# MCU_PWR.net
KiCad netlist of a schematic drawn in Altium Designer
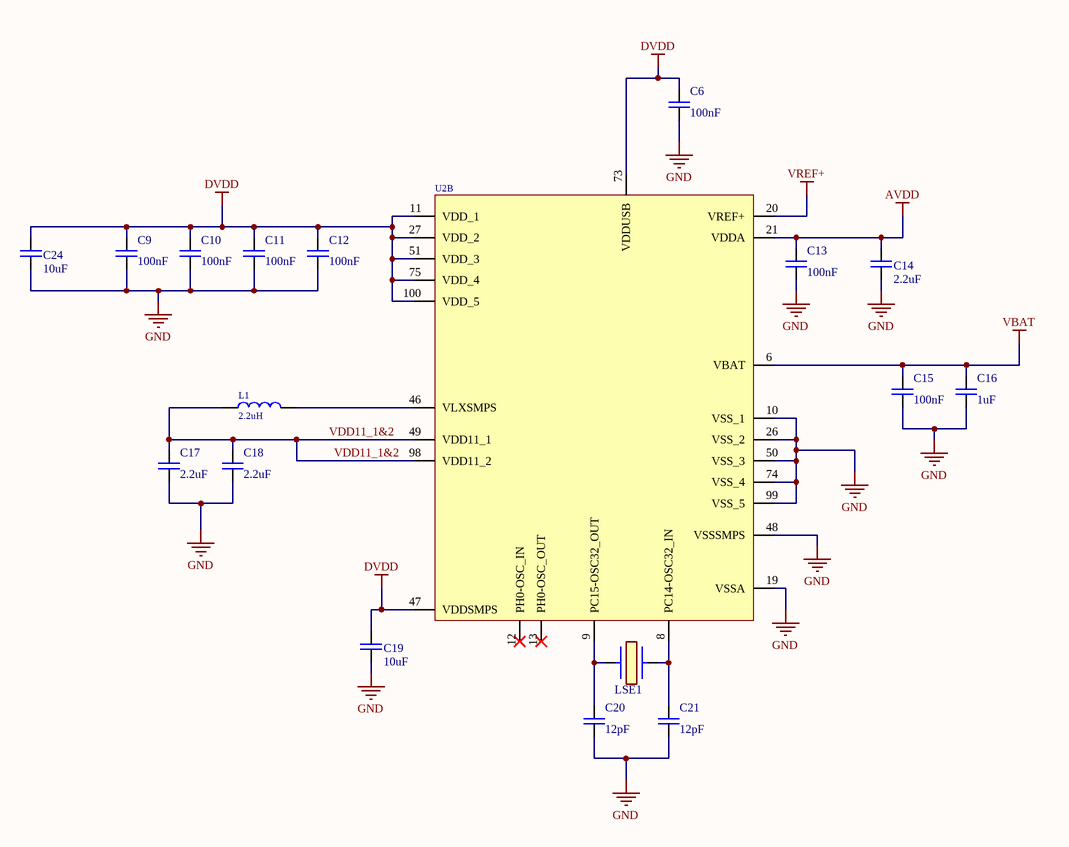
[diagram p0: MCU_PWR.SchDoc]

(export (version "E")
  (design (tool "Eeschema 10.0.6"))
  (components
    (comp (ref "C6")
      (value "100nF")
      (footprint "CAP_SM0805_YAGEOCC2_N")
      (description "CAP 100nF SM0805 X7R 50V YAGEO CC2")
      (fields
        (field (name "MANUFACTURER") "Yageo")
        (field (name "MANUFACTURER PART NUMBER") "CC0805KRX7R9BB104")
      )
      (libsource (lib "Yageo") (part "CC0805KRX7R9BB104"))
    )
    (comp (ref "C9")
      (value "100nF")
      (footprint "CAP_SM0805_YAGEOCC2_N")
      (description "CAP 100nF SM0805 X7R 50V YAGEO CC2")
      (fields
        (field (name "MANUFACTURER") "Yageo")
        (field (name "MANUFACTURER PART NUMBER") "CC0805KRX7R9BB104")
      )
      (libsource (lib "Yageo") (part "CC0805KRX7R9BB104"))
    )
    (comp (ref "C10")
      (value "100nF")
      (footprint "CAP_SM0805_YAGEOCC2_N")
      (description "CAP 100nF SM0805 X7R 50V YAGEO CC2")
      (fields
        (field (name "MANUFACTURER") "Yageo")
        (field (name "MANUFACTURER PART NUMBER") "CC0805KRX7R9BB104")
      )
      (libsource (lib "Yageo") (part "CC0805KRX7R9BB104"))
    )
    (comp (ref "C11")
      (value "100nF")
      (footprint "CAP_SM0805_YAGEOCC2_N")
      (description "CAP 100nF SM0805 X7R 50V YAGEO CC2")
      (fields
        (field (name "MANUFACTURER") "Yageo")
        (field (name "MANUFACTURER PART NUMBER") "CC0805KRX7R9BB104")
      )
      (libsource (lib "Yageo") (part "CC0805KRX7R9BB104"))
    )
    (comp (ref "C12")
      (value "100nF")
      (footprint "CAP_SM0805_YAGEOCC2_N")
      (description "CAP 100nF SM0805 X7R 50V YAGEO CC2")
      (fields
        (field (name "MANUFACTURER") "Yageo")
        (field (name "MANUFACTURER PART NUMBER") "CC0805KRX7R9BB104")
      )
      (libsource (lib "Yageo") (part "CC0805KRX7R9BB104"))
    )
    (comp (ref "C13")
      (value "100nF")
      (footprint "CAP_SM0805_YAGEOCC2_N")
      (description "CAP 100nF SM0805 X7R 50V YAGEO CC2")
      (fields
        (field (name "MANUFACTURER") "Yageo")
        (field (name "MANUFACTURER PART NUMBER") "CC0805KRX7R9BB104")
      )
      (libsource (lib "Yageo") (part "CC0805KRX7R9BB104"))
    )
    (comp (ref "C14")
      (value "2.2uF")
      (footprint "CAP_SM0805_YAGEOCC2_N")
      (description "CAP 2u2F SM0805 X7R 25V YAGEO CC2")
      (fields
        (field (name "MANUFACTURER") "Yageo")
        (field (name "MANUFACTURER PART NUMBER") "CC0805KKX7R8BB225")
      )
      (libsource (lib "Yageo") (part "CC0805KKX7R8BB225"))
    )
    (comp (ref "C15")
      (value "100nF")
      (footprint "CAP_SM0805_YAGEOCC2_N")
      (description "CAP 100nF SM0805 X7R 50V YAGEO CC2")
      (fields
        (field (name "MANUFACTURER") "Yageo")
        (field (name "MANUFACTURER PART NUMBER") "CC0805KRX7R9BB104")
      )
      (libsource (lib "Yageo") (part "CC0805KRX7R9BB104"))
    )
    (comp (ref "C16")
      (value "1uF")
      (footprint "CAP_SM0805_YAGEOCC2_N")
      (description "CAP 1uF SM0805 X7R 25V YAGEO CC2")
      (fields
        (field (name "MANUFACTURER") "Yageo")
        (field (name "MANUFACTURER PART NUMBER") "CC0805KKX7R8BB105")
      )
      (libsource (lib "Yageo") (part "CC0805KKX7R8BB105"))
    )
    (comp (ref "C17")
      (value "2.2uF")
      (footprint "CAP_SM0805_YAGEOCC2_N")
      (description "CAP 2u2F SM0805 X7R 25V YAGEO CC2")
      (fields
        (field (name "MANUFACTURER") "Yageo")
        (field (name "MANUFACTURER PART NUMBER") "CC0805KKX7R8BB225")
      )
      (libsource (lib "Yageo") (part "CC0805KKX7R8BB225"))
    )
    (comp (ref "C18")
      (value "2.2uF")
      (footprint "CAP_SM0805_YAGEOCC2_N")
      (description "CAP 2u2F SM0805 X7R 25V YAGEO CC2")
      (fields
        (field (name "MANUFACTURER") "Yageo")
        (field (name "MANUFACTURER PART NUMBER") "CC0805KKX7R8BB225")
      )
      (libsource (lib "Yageo") (part "CC0805KKX7R8BB225"))
    )
    (comp (ref "C19")
      (value "10uF")
      (footprint "CAP_SM0805_YAGEOCC2_N")
      (description "CAP 10uF SM0805 X5R 25V YAGEO")
      (fields
        (field (name "MANUFACTURER") "Yageo")
        (field (name "MANUFACTURER PART NUMBER") "CC0805KKX5R8BB106")
      )
      (libsource (lib "Yageo") (part "CC0805KKX5R8BB106"))
    )
    (comp (ref "C20")
      (value "12pF")
      (footprint "CAP_SM0805_YAGEOCC2_N")
      (description "CAP 12pF SM0805 NPO 50V YAGEO CC2")
      (fields
        (field (name "MANUFACTURER") "Yageo")
        (field (name "MANUFACTURER PART NUMBER") "CC0805JRNPO9BN120")
      )
      (libsource (lib "Yageo") (part "CC0805JRNPO9BN120"))
    )
    (comp (ref "C21")
      (value "12pF")
      (footprint "CAP_SM0805_YAGEOCC2_N")
      (description "CAP 12pF SM0805 NPO 50V YAGEO CC2")
      (fields
        (field (name "MANUFACTURER") "Yageo")
        (field (name "MANUFACTURER PART NUMBER") "CC0805JRNPO9BN120")
      )
      (libsource (lib "Yageo") (part "CC0805JRNPO9BN120"))
    )
    (comp (ref "C24")
      (value "10uF")
      (footprint "CAP_SM0805_YAGEOCC2_N")
      (description "CAP 10uF SM0805 X5R 25V YAGEO")
      (fields
        (field (name "MANUFACTURER") "Yageo")
        (field (name "MANUFACTURER PART NUMBER") "CC0805KKX5R8BB106")
      )
      (libsource (lib "Yageo") (part "CC0805KKX5R8BB106"))
    )
    (comp (ref "L1")
      (value "2.2uH")
      (footprint "LQM21PN2R2MGHL")
      (description "Inductores de potencia - SMD 2.2 UH 20%")
      (fields
        (field (name "MANUFACTURER") "Murata Electronics")
        (field (name "MANUFACTURER PART NUMBER") "LQM21PN2R2MGHL")
      )
      (libsource (lib "Inductores") (part "LQM21PN2R2MGHL"))
    )
    (comp (ref "LSE1")
      (value "32,768 kHz")
      (footprint "SC-32S32.768kHz20PPM12.5pF")
      (description "Cristal Oscilador 32.768 kHz, 12.5pF")
      (fields
        (field (name "MANUFACTURER") "Seiko")
        (field (name "MANUFACTURER PART NUMBER") "SC32S-12.5PF20PPM")
      )
      (libsource (lib "Osciladores") (part "SC32S-12.5PF20PPM"))
    )
    (comp (ref "U2")
      (value "STM32U575VI_1")
      (footprint "STM32U575VI")
      (fields (field (name "MANUFACTURER") "ST") (field (name "MANUFACTURER PART NUMBER") "STM32U575VIT6Q"))
      (libsource (lib "Microcontroladores") (part "STM32U575VI_1"))
    )
  )
  (nets
    (net (code "1") (name "/VDD11_1&2") (class "Default")
      (node (ref "C17") (pin "1") (pintype "passive"))
      (node (ref "C18") (pin "1") (pintype "passive"))
      (node (ref "L1") (pin "1") (pinfunction "1_1") (pintype "passive"))
      (node (ref "U2") (pin "49") (pinfunction "VDD11_1_49") (pintype "passive"))
      (node (ref "U2") (pin "98") (pinfunction "VDD11_2_98") (pintype "passive"))
    )
    (net (code "2") (name "AVDD") (class "Default")
      (node (ref "C13") (pin "1") (pintype "passive"))
      (node (ref "C14") (pin "1") (pintype "passive"))
      (node (ref "U2") (pin "21") (pinfunction "VDDA_21") (pintype "passive"))
    )
    (net (code "3") (name "DVDD") (class "Default")
      (node (ref "C10") (pin "1") (pintype "passive"))
      (node (ref "C11") (pin "1") (pintype "passive"))
      (node (ref "C12") (pin "1") (pintype "passive"))
      (node (ref "C19") (pin "1") (pintype "passive"))
      (node (ref "C24") (pin "1") (pintype "passive"))
      (node (ref "C6") (pin "1") (pintype "passive"))
      (node (ref "C9") (pin "1") (pintype "passive"))
      (node (ref "U2") (pin "100") (pinfunction "VDD_5_100") (pintype "passive"))
      (node (ref "U2") (pin "11") (pinfunction "VDD_1_11") (pintype "passive"))
      (node (ref "U2") (pin "27") (pinfunction "VDD_2_27") (pintype "passive"))
      (node (ref "U2") (pin "47") (pinfunction "VDDSMPS_47") (pintype "passive"))
      (node (ref "U2") (pin "51") (pinfunction "VDD_3_51") (pintype "passive"))
      (node (ref "U2") (pin "73") (pinfunction "VDDUSB_73") (pintype "passive"))
      (node (ref "U2") (pin "75") (pinfunction "VDD_4_75") (pintype "passive"))
    )
    (net (code "4") (name "GND") (class "Default")
      (node (ref "C10") (pin "2") (pintype "passive"))
      (node (ref "C11") (pin "2") (pintype "passive"))
      (node (ref "C12") (pin "2") (pintype "passive"))
      (node (ref "C13") (pin "2") (pintype "passive"))
      (node (ref "C14") (pin "2") (pintype "passive"))
      (node (ref "C15") (pin "2") (pintype "passive"))
      (node (ref "C16") (pin "2") (pintype "passive"))
      (node (ref "C17") (pin "2") (pintype "passive"))
      (node (ref "C18") (pin "2") (pintype "passive"))
      (node (ref "C19") (pin "2") (pintype "passive"))
      (node (ref "C20") (pin "2") (pintype "passive"))
      (node (ref "C21") (pin "2") (pintype "passive"))
      (node (ref "C24") (pin "2") (pintype "passive"))
      (node (ref "C6") (pin "2") (pintype "passive"))
      (node (ref "C9") (pin "2") (pintype "passive"))
      (node (ref "U2") (pin "10") (pinfunction "VSS_1_10") (pintype "passive"))
      (node (ref "U2") (pin "19") (pinfunction "VSSA_19") (pintype "passive"))
      (node (ref "U2") (pin "26") (pinfunction "VSS_2_26") (pintype "passive"))
      (node (ref "U2") (pin "48") (pinfunction "VSSSMPS_48") (pintype "passive"))
      (node (ref "U2") (pin "50") (pinfunction "VSS_3_50") (pintype "passive"))
      (node (ref "U2") (pin "74") (pinfunction "VSS_4_74") (pintype "passive"))
      (node (ref "U2") (pin "99") (pinfunction "VSS_5_99") (pintype "passive"))
    )
    (net (code "5") (name "Net-(U2B-PC14-OSC32_IN)") (class "Default")
      (node (ref "C21") (pin "1") (pintype "passive"))
      (node (ref "LSE1") (pin "2") (pinfunction "2_2") (pintype "passive"))
      (node (ref "U2") (pin "8") (pinfunction "PC14-OSC32_IN_8") (pintype "passive"))
    )
    (net (code "6") (name "Net-(U2B-PC15-OSC32_OUT)") (class "Default")
      (node (ref "C20") (pin "1") (pintype "passive"))
      (node (ref "LSE1") (pin "1") (pinfunction "1_1") (pintype "passive"))
      (node (ref "U2") (pin "9") (pinfunction "PC15-OSC32_OUT_9") (pintype "passive"))
    )
    (net (code "7") (name "Net-(U2B-VLXSMPS)") (class "Default")
      (node (ref "L1") (pin "2") (pinfunction "2_2") (pintype "passive"))
      (node (ref "U2") (pin "46") (pinfunction "VLXSMPS_46") (pintype "passive"))
    )
    (net (code "8") (name "VBAT") (class "Default")
      (node (ref "C15") (pin "1") (pintype "passive"))
      (node (ref "C16") (pin "1") (pintype "passive"))
      (node (ref "U2") (pin "6") (pinfunction "VBAT_6") (pintype "passive"))
    )
    (net (code "9") (name "VREF+") (class "Default")
      (node (ref "U2") (pin "20") (pinfunction "VREF+_20") (pintype "passive"))
    )
    (net (code "10") (name "unconnected-(U2B-PH0-OSC_IN-Pad12)") (class "Default")
      (node (ref "U2") (pin "12") (pinfunction "PH0-OSC_IN_12") (pintype "passive+no_connect"))
    )
    (net (code "11") (name "unconnected-(U2B-PH0-OSC_OUT-Pad13)") (class "Default")
      (node (ref "U2") (pin "13") (pinfunction "PH0-OSC_OUT_13") (pintype "passive+no_connect"))
    )
  )
)
